# 7segement4digits1badidea-many-digits-mk-.net
KiCad netlist of a schematic drawn in EAGLE
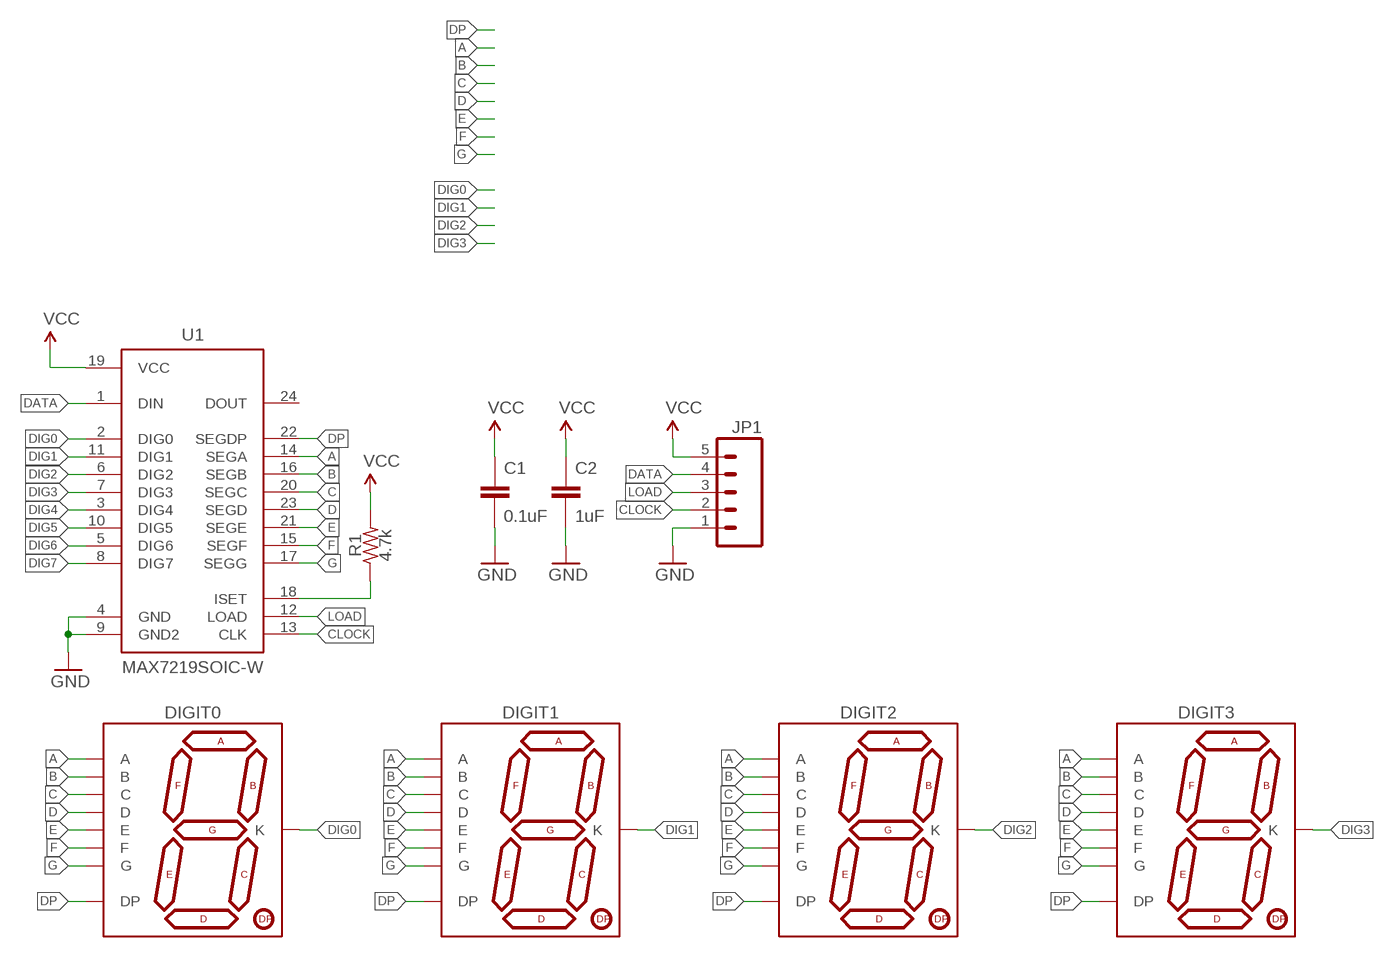
[diagram p0: schematic, sheet 1]

(export (version "E")
  (design (tool "Eeschema 10.0.6"))
  (components
    (comp (ref "C1")
      (value "0.1uF")
      (footprint "eagle-import:C0603")
      (libsource (lib "eagle-import") (part "CAPACITOR-CERAMICC0603"))
    )
    (comp (ref "C2")
      (value "1uF")
      (footprint "eagle-import:C0805")
      (libsource (lib "eagle-import") (part "CAPACITOR-CERAMICC0805"))
    )
    (comp (ref "DIGIT0")
      (value "7SEG_1DIGPTH-10MM")
      (footprint "eagle-import:7SEG_1DIG_10MM")
      (libsource (lib "eagle-import") (part "7SEG_1DIGPTH-10MM"))
    )
    (comp (ref "DIGIT1")
      (value "7SEG_1DIGPTH-10MM")
      (footprint "eagle-import:7SEG_1DIG_10MM")
      (libsource (lib "eagle-import") (part "7SEG_1DIGPTH-10MM"))
    )
    (comp (ref "DIGIT2")
      (value "7SEG_1DIGPTH-10MM")
      (footprint "eagle-import:7SEG_1DIG_10MM")
      (libsource (lib "eagle-import") (part "7SEG_1DIGPTH-10MM"))
    )
    (comp (ref "DIGIT3")
      (value "7SEG_1DIGPTH-10MM")
      (footprint "eagle-import:7SEG_1DIG_10MM")
      (libsource (lib "eagle-import") (part "7SEG_1DIGPTH-10MM"))
    )
    (comp (ref "JP1")
      (value "M05JST-PH-VERT-PTH")
      (footprint "eagle-import:JST-5-PH-VERT-PTH")
      (libsource (lib "eagle-import") (part "M05JST-PH-VERT-PTH"))
    )
    (comp (ref "R1")
      (value "4.7k")
      (footprint "eagle-import:R0603")
      (libsource (lib "eagle-import") (part "RESISTORR0603"))
    )
    (comp (ref "U1")
      (value "MAX7219SOIC-W")
      (footprint "eagle-import:SO24W")
      (libsource (lib "eagle-import") (part "MAX7219SOIC-W"))
    )
  )
  (nets
    (net (code "1") (name "A") (class "Default")
      (node (ref "DIGIT0") (pin "10") (pinfunction "A_10") (pintype "bidirectional"))
      (node (ref "DIGIT1") (pin "10") (pinfunction "A_10") (pintype "bidirectional"))
      (node (ref "DIGIT2") (pin "10") (pinfunction "A_10") (pintype "bidirectional"))
      (node (ref "DIGIT3") (pin "10") (pinfunction "A_10") (pintype "bidirectional"))
      (node (ref "U1") (pin "14") (pinfunction "SEGA_14") (pintype "bidirectional"))
    )
    (net (code "2") (name "B") (class "Default")
      (node (ref "DIGIT0") (pin "9") (pinfunction "B_9") (pintype "bidirectional"))
      (node (ref "DIGIT1") (pin "9") (pinfunction "B_9") (pintype "bidirectional"))
      (node (ref "DIGIT2") (pin "9") (pinfunction "B_9") (pintype "bidirectional"))
      (node (ref "DIGIT3") (pin "9") (pinfunction "B_9") (pintype "bidirectional"))
      (node (ref "U1") (pin "16") (pinfunction "SEGB_16") (pintype "bidirectional"))
    )
    (net (code "3") (name "C") (class "Default")
      (node (ref "DIGIT0") (pin "8") (pinfunction "C_8") (pintype "bidirectional"))
      (node (ref "DIGIT1") (pin "8") (pinfunction "C_8") (pintype "bidirectional"))
      (node (ref "DIGIT2") (pin "8") (pinfunction "C_8") (pintype "bidirectional"))
      (node (ref "DIGIT3") (pin "8") (pinfunction "C_8") (pintype "bidirectional"))
      (node (ref "U1") (pin "20") (pinfunction "SEGC_20") (pintype "bidirectional"))
    )
    (net (code "4") (name "CLOCK") (class "Default")
      (node (ref "JP1") (pin "2") (pinfunction "2_2") (pintype "passive"))
      (node (ref "U1") (pin "13") (pinfunction "CLK_13") (pintype "bidirectional"))
    )
    (net (code "5") (name "D") (class "Default")
      (node (ref "DIGIT0") (pin "5") (pinfunction "D_5") (pintype "bidirectional"))
      (node (ref "DIGIT1") (pin "5") (pinfunction "D_5") (pintype "bidirectional"))
      (node (ref "DIGIT2") (pin "5") (pinfunction "D_5") (pintype "bidirectional"))
      (node (ref "DIGIT3") (pin "5") (pinfunction "D_5") (pintype "bidirectional"))
      (node (ref "U1") (pin "23") (pinfunction "SEGD_23") (pintype "bidirectional"))
    )
    (net (code "6") (name "DATA") (class "Default")
      (node (ref "JP1") (pin "4") (pinfunction "4_4") (pintype "passive"))
      (node (ref "U1") (pin "1") (pinfunction "DIN_1") (pintype "bidirectional"))
    )
    (net (code "7") (name "DIG0") (class "Default")
      (node (ref "DIGIT0") (pin "1") (pinfunction "K_1") (pintype "bidirectional"))
      (node (ref "DIGIT0") (pin "6") (pinfunction "K_6") (pintype "bidirectional"))
      (node (ref "U1") (pin "2") (pinfunction "DIG0_2") (pintype "bidirectional"))
    )
    (net (code "8") (name "DIG1") (class "Default")
      (node (ref "DIGIT1") (pin "1") (pinfunction "K_1") (pintype "bidirectional"))
      (node (ref "DIGIT1") (pin "6") (pinfunction "K_6") (pintype "bidirectional"))
      (node (ref "U1") (pin "11") (pinfunction "DIG1_11") (pintype "bidirectional"))
    )
    (net (code "9") (name "DIG2") (class "Default")
      (node (ref "DIGIT2") (pin "1") (pinfunction "K_1") (pintype "bidirectional"))
      (node (ref "DIGIT2") (pin "6") (pinfunction "K_6") (pintype "bidirectional"))
      (node (ref "U1") (pin "6") (pinfunction "DIG2_6") (pintype "bidirectional"))
    )
    (net (code "10") (name "DIG3") (class "Default")
      (node (ref "DIGIT3") (pin "1") (pinfunction "K_1") (pintype "bidirectional"))
      (node (ref "DIGIT3") (pin "6") (pinfunction "K_6") (pintype "bidirectional"))
      (node (ref "U1") (pin "7") (pinfunction "DIG3_7") (pintype "bidirectional"))
    )
    (net (code "11") (name "DIG4") (class "Default")
      (node (ref "U1") (pin "3") (pinfunction "DIG4_3") (pintype "bidirectional"))
    )
    (net (code "12") (name "DIG5") (class "Default")
      (node (ref "U1") (pin "10") (pinfunction "DIG5_10") (pintype "bidirectional"))
    )
    (net (code "13") (name "DIG6") (class "Default")
      (node (ref "U1") (pin "5") (pinfunction "DIG6_5") (pintype "bidirectional"))
    )
    (net (code "14") (name "DIG7") (class "Default")
      (node (ref "U1") (pin "8") (pinfunction "DIG7_8") (pintype "bidirectional"))
    )
    (net (code "15") (name "DP") (class "Default")
      (node (ref "DIGIT0") (pin "7") (pinfunction "DP_7") (pintype "bidirectional"))
      (node (ref "DIGIT1") (pin "7") (pinfunction "DP_7") (pintype "bidirectional"))
      (node (ref "DIGIT2") (pin "7") (pinfunction "DP_7") (pintype "bidirectional"))
      (node (ref "DIGIT3") (pin "7") (pinfunction "DP_7") (pintype "bidirectional"))
      (node (ref "U1") (pin "22") (pinfunction "SEGDP_22") (pintype "bidirectional"))
    )
    (net (code "16") (name "E") (class "Default")
      (node (ref "DIGIT0") (pin "4") (pinfunction "E_4") (pintype "bidirectional"))
      (node (ref "DIGIT1") (pin "4") (pinfunction "E_4") (pintype "bidirectional"))
      (node (ref "DIGIT2") (pin "4") (pinfunction "E_4") (pintype "bidirectional"))
      (node (ref "DIGIT3") (pin "4") (pinfunction "E_4") (pintype "bidirectional"))
      (node (ref "U1") (pin "21") (pinfunction "SEGE_21") (pintype "bidirectional"))
    )
    (net (code "17") (name "F") (class "Default")
      (node (ref "DIGIT0") (pin "2") (pinfunction "F_2") (pintype "bidirectional"))
      (node (ref "DIGIT1") (pin "2") (pinfunction "F_2") (pintype "bidirectional"))
      (node (ref "DIGIT2") (pin "2") (pinfunction "F_2") (pintype "bidirectional"))
      (node (ref "DIGIT3") (pin "2") (pinfunction "F_2") (pintype "bidirectional"))
      (node (ref "U1") (pin "15") (pinfunction "SEGF_15") (pintype "bidirectional"))
    )
    (net (code "18") (name "G") (class "Default")
      (node (ref "DIGIT0") (pin "3") (pinfunction "G_3") (pintype "bidirectional"))
      (node (ref "DIGIT1") (pin "3") (pinfunction "G_3") (pintype "bidirectional"))
      (node (ref "DIGIT2") (pin "3") (pinfunction "G_3") (pintype "bidirectional"))
      (node (ref "DIGIT3") (pin "3") (pinfunction "G_3") (pintype "bidirectional"))
      (node (ref "U1") (pin "17") (pinfunction "SEGG_17") (pintype "bidirectional"))
    )
    (net (code "19") (name "GND") (class "Default")
      (node (ref "C1") (pin "2") (pinfunction "2_2") (pintype "passive"))
      (node (ref "C2") (pin "2") (pinfunction "2_2") (pintype "passive"))
      (node (ref "JP1") (pin "1") (pinfunction "1_1") (pintype "passive"))
      (node (ref "U1") (pin "4") (pinfunction "GND_4") (pintype "bidirectional"))
      (node (ref "U1") (pin "9") (pinfunction "GND2_9") (pintype "bidirectional"))
    )
    (net (code "20") (name "LOAD") (class "Default")
      (node (ref "JP1") (pin "3") (pinfunction "3_3") (pintype "passive"))
      (node (ref "U1") (pin "12") (pinfunction "LOAD_12") (pintype "bidirectional"))
    )
    (net (code "21") (name "Net-(U1-ISET)") (class "Default")
      (node (ref "R1") (pin "1") (pinfunction "1_1") (pintype "passive"))
      (node (ref "U1") (pin "18") (pinfunction "ISET_18") (pintype "bidirectional"))
    )
    (net (code "22") (name "VCC") (class "Default")
      (node (ref "C1") (pin "1") (pinfunction "1_1") (pintype "passive"))
      (node (ref "C2") (pin "1") (pinfunction "1_1") (pintype "passive"))
      (node (ref "JP1") (pin "5") (pinfunction "5_5") (pintype "passive"))
      (node (ref "R1") (pin "2") (pinfunction "2_2") (pintype "passive"))
      (node (ref "U1") (pin "19") (pinfunction "VCC_19") (pintype "bidirectional"))
    )
    (net (code "23") (name "unconnected-(U1-DOUT-Pad24)") (class "Default")
      (node (ref "U1") (pin "24") (pinfunction "DOUT_24") (pintype "bidirectional"))
    )
  )
)
